# LAN7800-Board.net
KiCad netlist of a schematic drawn in Altium Designer
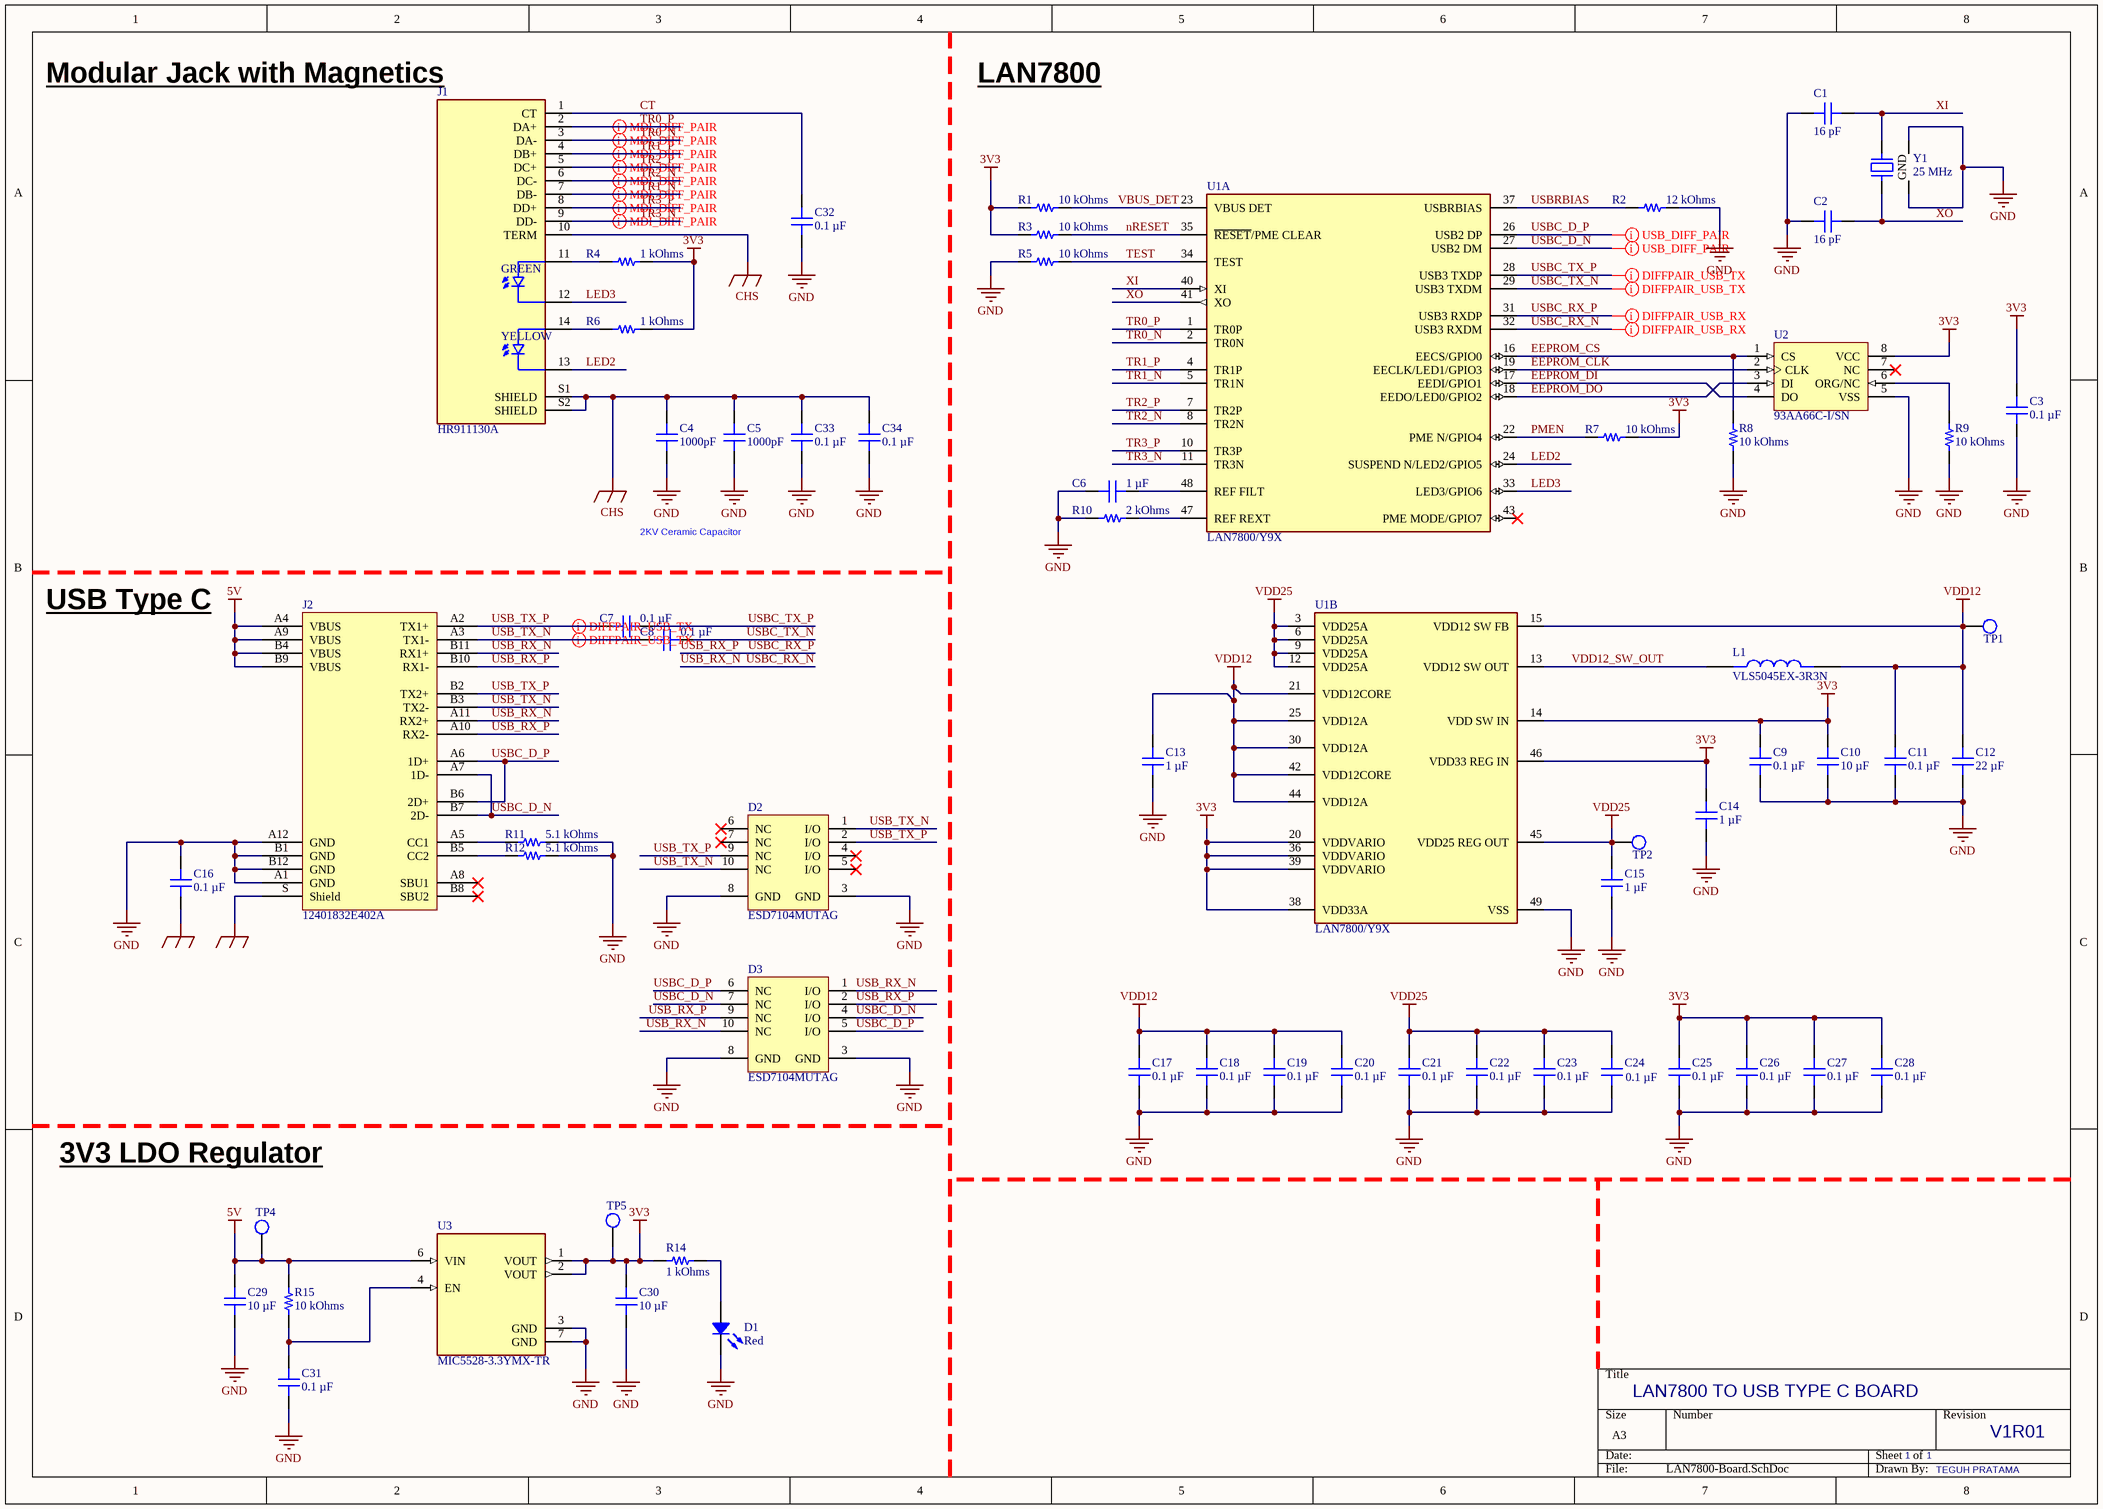
[diagram p0: LAN7800-Board.SchDoc]

(export (version "E")
  (design (tool "Eeschema 10.0.6"))
  (components
    (comp (ref "C1")
      (value "16 pF")
      (footprint "CAP 0402_1005")
      (description "CAP CER 16PF 50V C0G/NP0 0402")
      (fields (field (name "PART NUMBER") "CBR04C160F5GAC") (field (name "MANUFACTURER") "KEMET"))
      (libsource (lib "Celestial Altium Library - altium_library") (part "Capacitor"))
    )
    (comp (ref "C2")
      (value "16 pF")
      (footprint "CAP 0402_1005")
      (description "CAP CER 16PF 50V C0G/NP0 0402")
      (fields (field (name "PART NUMBER") "CBR04C160F5GAC") (field (name "MANUFACTURER") "KEMET"))
      (libsource (lib "Celestial Altium Library - altium_library") (part "Capacitor"))
    )
    (comp (ref "C3")
      (value "0.1 µF")
      (footprint "CAP 0402_1005")
      (description "CAP CER 0402 0.1UF 16V X7R 10%")
      (fields (field (name "PART NUMBER") "C0402C104K4RECAUTO") (field (name "MANUFACTURER") "KEMET"))
      (libsource (lib "Celestial Altium Library - altium_library") (part "Capacitor"))
    )
    (comp (ref "C4")
      (value "1000pF")
      (footprint "CAP 1812_4532 2.8MM")
      (description "CAP CER 1000PF 2.5KV X7R 1812")
      (fields (field (name "PART NUMBER") "1812WC102KAT1A") (field (name "MANUFACTURER") "AVX Corporation"))
      (libsource (lib "Celestial Altium Library - altium_library") (part "Capacitor"))
    )
    (comp (ref "C5")
      (value "1000pF")
      (footprint "CAP 1812_4532 2.8MM")
      (description "CAP CER 1000PF 2.5KV X7R 1812")
      (fields (field (name "PART NUMBER") "1812WC102KAT1A") (field (name "MANUFACTURER") "AVX Corporation"))
      (libsource (lib "Celestial Altium Library - altium_library") (part "Capacitor"))
    )
    (comp (ref "C6")
      (value "1 µF")
      (footprint "CAP 0402_1005")
      (description "CAP CER 1UF 10V X7S 0402")
      (fields
        (field (name "PART NUMBER") "GRM155C71A105KE11D")
        (field (name "MANUFACTURER") "Murata Electronics")
      )
      (libsource (lib "Celestial Altium Library - altium_library") (part "Capacitor"))
    )
    (comp (ref "C7")
      (value "0.1 µF")
      (footprint "CAP 0402_1005")
      (description "CAP CER 0.1UF 50V X5R 0402")
      (fields
        (field (name "PART NUMBER") "CGA2B3X5R1H104M050BB")
        (field (name "MANUFACTURER") "TDK Corporation")
      )
      (libsource (lib "Celestial Altium Library - altium_library") (part "Capacitor"))
    )
    (comp (ref "C8")
      (value "0.1 µF")
      (footprint "CAP 0402_1005")
      (description "CAP CER 0.1UF 50V X5R 0402")
      (fields
        (field (name "PART NUMBER") "CGA2B3X5R1H104M050BB")
        (field (name "MANUFACTURER") "TDK Corporation")
      )
      (libsource (lib "Celestial Altium Library - altium_library") (part "Capacitor"))
    )
    (comp (ref "C9")
      (value "0.1 µF")
      (footprint "CAP 0402_1005")
      (description "CAP CER 0402 0.1UF 16V X7R 10%")
      (fields (field (name "PART NUMBER") "C0402C104K4RECAUTO") (field (name "MANUFACTURER") "KEMET"))
      (libsource (lib "Celestial Altium Library - altium_library") (part "Capacitor"))
    )
    (comp (ref "C10")
      (value "10 µF")
      (footprint "CAP 0603_1608")
      (description "CAP CER 10UF 16V X5R 0603")
      (fields
        (field (name "PART NUMBER") "GRT188R61C106ME13D")
        (field (name "MANUFACTURER") "Murata Electronics")
      )
      (libsource (lib "Celestial Altium Library - altium_library") (part "Capacitor"))
    )
    (comp (ref "C11")
      (value "0.1 µF")
      (footprint "CAP 0402_1005")
      (description "CAP CER 0402 0.1UF 16V X7R 10%")
      (fields (field (name "PART NUMBER") "C0402C104K4RECAUTO") (field (name "MANUFACTURER") "KEMET"))
      (libsource (lib "Celestial Altium Library - altium_library") (part "Capacitor"))
    )
    (comp (ref "C12")
      (value "22 µF")
      (footprint "CAP 0603_1608")
      (description "CAP CER 22UF 10V X5R 0603")
      (fields
        (field (name "PART NUMBER") "C1608X5R1A226M080AC")
        (field (name "MANUFACTURER") "TDK Corporation")
      )
      (libsource (lib "Celestial Altium Library - altium_library") (part "Capacitor"))
    )
    (comp (ref "C13")
      (value "1 µF")
      (footprint "CAP 0402_1005")
      (description "CAP CER 1UF 10V X7S 0402")
      (fields
        (field (name "PART NUMBER") "GRM155C71A105KE11D")
        (field (name "MANUFACTURER") "Murata Electronics")
      )
      (libsource (lib "Celestial Altium Library - altium_library") (part "Capacitor"))
    )
    (comp (ref "C14")
      (value "1 µF")
      (footprint "CAP 0402_1005")
      (description "CAP CER 1UF 10V X7S 0402")
      (fields
        (field (name "PART NUMBER") "GRM155C71A105KE11D")
        (field (name "MANUFACTURER") "Murata Electronics")
      )
      (libsource (lib "Celestial Altium Library - altium_library") (part "Capacitor"))
    )
    (comp (ref "C15")
      (value "1 µF")
      (footprint "CAP 0402_1005")
      (description "CAP CER 1UF 10V X7S 0402")
      (fields
        (field (name "PART NUMBER") "GRM155C71A105KE11D")
        (field (name "MANUFACTURER") "Murata Electronics")
      )
      (libsource (lib "Celestial Altium Library - altium_library") (part "Capacitor"))
    )
    (comp (ref "C16")
      (value "0.1 µF")
      (footprint "CAP 0402_1005")
      (description "CAP CER 0.1UF 50V X5R 0402")
      (fields
        (field (name "PART NUMBER") "CGA2B3X5R1H104M050BB")
        (field (name "MANUFACTURER") "TDK Corporation")
      )
      (libsource (lib "Celestial Altium Library - altium_library") (part "Capacitor"))
    )
    (comp (ref "C17")
      (value "0.1 µF")
      (footprint "CAP 0402_1005")
      (description "CAP CER 0402 0.1UF 16V X7R 10%")
      (fields (field (name "PART NUMBER") "C0402C104K4RECAUTO") (field (name "MANUFACTURER") "KEMET"))
      (libsource (lib "Celestial Altium Library - altium_library") (part "Capacitor"))
    )
    (comp (ref "C18")
      (value "0.1 µF")
      (footprint "CAP 0402_1005")
      (description "CAP CER 0402 0.1UF 16V X7R 10%")
      (fields (field (name "PART NUMBER") "C0402C104K4RECAUTO") (field (name "MANUFACTURER") "KEMET"))
      (libsource (lib "Celestial Altium Library - altium_library") (part "Capacitor"))
    )
    (comp (ref "C19")
      (value "0.1 µF")
      (footprint "CAP 0402_1005")
      (description "CAP CER 0402 0.1UF 16V X7R 10%")
      (fields (field (name "PART NUMBER") "C0402C104K4RECAUTO") (field (name "MANUFACTURER") "KEMET"))
      (libsource (lib "Celestial Altium Library - altium_library") (part "Capacitor"))
    )
    (comp (ref "C20")
      (value "0.1 µF")
      (footprint "CAP 0402_1005")
      (description "CAP CER 0402 0.1UF 16V X7R 10%")
      (fields (field (name "PART NUMBER") "C0402C104K4RECAUTO") (field (name "MANUFACTURER") "KEMET"))
      (libsource (lib "Celestial Altium Library - altium_library") (part "Capacitor"))
    )
    (comp (ref "C21")
      (value "0.1 µF")
      (footprint "CAP 0402_1005")
      (description "CAP CER 0402 0.1UF 16V X7R 10%")
      (fields (field (name "PART NUMBER") "C0402C104K4RECAUTO") (field (name "MANUFACTURER") "KEMET"))
      (libsource (lib "Celestial Altium Library - altium_library") (part "Capacitor"))
    )
    (comp (ref "C22")
      (value "0.1 µF")
      (footprint "CAP 0402_1005")
      (description "CAP CER 0402 0.1UF 16V X7R 10%")
      (fields (field (name "PART NUMBER") "C0402C104K4RECAUTO") (field (name "MANUFACTURER") "KEMET"))
      (libsource (lib "Celestial Altium Library - altium_library") (part "Capacitor"))
    )
    (comp (ref "C23")
      (value "0.1 µF")
      (footprint "CAP 0402_1005")
      (description "CAP CER 0402 0.1UF 16V X7R 10%")
      (fields (field (name "PART NUMBER") "C0402C104K4RECAUTO") (field (name "MANUFACTURER") "KEMET"))
      (libsource (lib "Celestial Altium Library - altium_library") (part "Capacitor"))
    )
    (comp (ref "C24")
      (value "0.1 µF")
      (footprint "CAP 0402_1005")
      (description "CAP CER 0402 0.1UF 16V X7R 10%")
      (fields (field (name "PART NUMBER") "C0402C104K4RECAUTO") (field (name "MANUFACTURER") "KEMET"))
      (libsource (lib "Celestial Altium Library - altium_library") (part "Capacitor"))
    )
    (comp (ref "C25")
      (value "0.1 µF")
      (footprint "CAP 0402_1005")
      (description "CAP CER 0402 0.1UF 16V X7R 10%")
      (fields (field (name "PART NUMBER") "C0402C104K4RECAUTO") (field (name "MANUFACTURER") "KEMET"))
      (libsource (lib "Celestial Altium Library - altium_library") (part "Capacitor"))
    )
    (comp (ref "C26")
      (value "0.1 µF")
      (footprint "CAP 0402_1005")
      (description "CAP CER 0402 0.1UF 16V X7R 10%")
      (fields (field (name "PART NUMBER") "C0402C104K4RECAUTO") (field (name "MANUFACTURER") "KEMET"))
      (libsource (lib "Celestial Altium Library - altium_library") (part "Capacitor"))
    )
    (comp (ref "C27")
      (value "0.1 µF")
      (footprint "CAP 0402_1005")
      (description "CAP CER 0402 0.1UF 16V X7R 10%")
      (fields (field (name "PART NUMBER") "C0402C104K4RECAUTO") (field (name "MANUFACTURER") "KEMET"))
      (libsource (lib "Celestial Altium Library - altium_library") (part "Capacitor"))
    )
    (comp (ref "C28")
      (value "0.1 µF")
      (footprint "CAP 0402_1005")
      (description "CAP CER 0402 0.1UF 16V X7R 10%")
      (fields (field (name "PART NUMBER") "C0402C104K4RECAUTO") (field (name "MANUFACTURER") "KEMET"))
      (libsource (lib "Celestial Altium Library - altium_library") (part "Capacitor"))
    )
    (comp (ref "C29")
      (value "10 µF")
      (footprint "CAP 0603_1608")
      (description "CAP CER 10UF 16V X5R 0603")
      (fields
        (field (name "PART NUMBER") "GRT188R61C106ME13D")
        (field (name "MANUFACTURER") "Murata Electronics")
      )
      (libsource (lib "Celestial Altium Library - altium_library") (part "Capacitor"))
    )
    (comp (ref "C30")
      (value "10 µF")
      (footprint "CAP 0603_1608")
      (description "CAP CER 10UF 16V X5R 0603")
      (fields
        (field (name "PART NUMBER") "GRT188R61C106ME13D")
        (field (name "MANUFACTURER") "Murata Electronics")
      )
      (libsource (lib "Celestial Altium Library - altium_library") (part "Capacitor"))
    )
    (comp (ref "C31")
      (value "0.1 µF")
      (footprint "CAP 0402_1005")
      (description "CAP CER 0402 0.1UF 16V X7R 10%")
      (fields (field (name "PART NUMBER") "C0402C104K4RECAUTO") (field (name "MANUFACTURER") "KEMET"))
      (libsource (lib "Celestial Altium Library - altium_library") (part "Capacitor"))
    )
    (comp (ref "C32")
      (value "0.1 µF")
      (footprint "CAP 0402_1005")
      (description "CAP CER 0402 0.1UF 16V X7R 10%")
      (fields (field (name "PART NUMBER") "C0402C104K4RECAUTO") (field (name "MANUFACTURER") "KEMET"))
      (libsource (lib "Celestial Altium Library - altium_library") (part "Capacitor"))
    )
    (comp (ref "C33")
      (value "0.1 µF")
      (footprint "CAP 0402_1005")
      (description "CAP CER 0402 0.1UF 16V X7R 10%")
      (fields (field (name "PART NUMBER") "C0402C104K4RECAUTO") (field (name "MANUFACTURER") "KEMET"))
      (libsource (lib "Celestial Altium Library - altium_library") (part "Capacitor"))
    )
    (comp (ref "C34")
      (value "0.1 µF")
      (footprint "CAP 0402_1005")
      (description "CAP CER 0402 0.1UF 16V X7R 10%")
      (fields (field (name "PART NUMBER") "C0402C104K4RECAUTO") (field (name "MANUFACTURER") "KEMET"))
      (libsource (lib "Celestial Altium Library - altium_library") (part "Capacitor"))
    )
    (comp (ref "D1")
      (value "Red")
      (footprint "LED 0603_1608 RED")
      (description "HIGH BRIGHTNESS LENS TYPE, RED C")
      (fields (field (name "PART NUMBER") "CSL0902VT1C") (field (name "MANUFACTURER") "Rohm Semiconductor"))
      (libsource (lib "Celestial Altium Library - altium_library") (part "LED"))
    )
    (comp (ref "D2")
      (value "ESD7104MUTAG")
      (footprint "ONSC-UDFN-10-517BB-01_V")
      (fields (field (name "MANUFACTURER") "On Semiconductor"))
      (libsource (lib "Diodes - Transient Voltage Supressor") (part "ESD7104MUTAG"))
    )
    (comp (ref "D3")
      (value "ESD7104MUTAG")
      (footprint "ONSC-UDFN-10-517BB-01_V")
      (fields (field (name "MANUFACTURER") "On Semiconductor"))
      (libsource (lib "Diodes - Transient Voltage Supressor") (part "ESD7104MUTAG"))
    )
    (comp (ref "J1")
      (value "HR911130A")
      (footprint "HANRUN_HR911130A")
      (description "Gigabit Ethernet with Magnetics")
      (fields (field (name "MF") "hanrun"))
      (libsource (lib "Connector - Modular Jack with Magnetics") (part "HR911130A"))
    )
    (comp (ref "J2")
      (value "12401832E402A")
      (footprint "GCT_USB4056-03-A_REVA2")
      (description "24 Position Hybrid Top Mount USB Type C 3.2 Gen Receptacle")
      (fields
        (field (name "MANUFACTURER") "Global Connector Technology")
        (field (name "MANUFACTURER PART NUMBER") "USB4056-03-A")
      )
      (libsource (lib "Connector - USB") (part "USB4056-03-A"))
    )
    (comp (ref "L1")
      (value "VLS5045EX-3R3N")
      (footprint "IND_VLS5045EX-3R3N")
      (description "General Purpose Inductor, 3.3uH, 30%, 1 Element, Ferrite-Core, SMD, 2020")
      (fields (field (name "MF") "TDK"))
      (libsource (lib "Inductor") (part "VLS5045EX-3R3N"))
    )
    (comp (ref "R1")
      (value "10 kOhms")
      (footprint "RES 0402_1005")
      (description "RES 10K OHM 0.1% 1/10W 0402")
      (fields
        (field (name "PART NUMBER") "RP73PF1E10KBTD")
        (field (name "MANUFACTURER") "TE Connectivity Passive Product")
      )
      (libsource (lib "Celestial Altium Library - altium_library") (part "Resistor"))
    )
    (comp (ref "R2")
      (value "12 kOhms")
      (footprint "RES 0402_1005")
      (description "RES SMD 12K OHM 0.1% 1/16W 0402")
      (fields
        (field (name "PART NUMBER") "CPF0402B12KE1")
        (field (name "MANUFACTURER") "TE Connectivity Passive Product")
      )
      (libsource (lib "Celestial Altium Library - altium_library") (part "Resistor"))
    )
    (comp (ref "R3")
      (value "10 kOhms")
      (footprint "RES 0402_1005")
      (description "RES 10K OHM 0.1% 1/10W 0402")
      (fields
        (field (name "PART NUMBER") "RP73PF1E10KBTD")
        (field (name "MANUFACTURER") "TE Connectivity Passive Product")
      )
      (libsource (lib "Celestial Altium Library - altium_library") (part "Resistor"))
    )
    (comp (ref "R4")
      (value "1 kOhms")
      (footprint "RES 0402_1005")
      (description "RES SMD 1K OHM 0.1% 1/16W 0402")
      (fields (field (name "PART NUMBER") "AT0402BRD071KL") (field (name "MANUFACTURER") "Yageo"))
      (libsource (lib "Celestial Altium Library - altium_library") (part "Resistor"))
    )
    (comp (ref "R5")
      (value "10 kOhms")
      (footprint "RES 0402_1005")
      (description "RES 10K OHM 0.1% 1/10W 0402")
      (fields
        (field (name "PART NUMBER") "RP73PF1E10KBTD")
        (field (name "MANUFACTURER") "TE Connectivity Passive Product")
      )
      (libsource (lib "Celestial Altium Library - altium_library") (part "Resistor"))
    )
    (comp (ref "R6")
      (value "1 kOhms")
      (footprint "RES 0402_1005")
      (description "RES SMD 1K OHM 0.1% 1/16W 0402")
      (fields (field (name "PART NUMBER") "AT0402BRD071KL") (field (name "MANUFACTURER") "Yageo"))
      (libsource (lib "Celestial Altium Library - altium_library") (part "Resistor"))
    )
    (comp (ref "R7")
      (value "10 kOhms")
      (footprint "RES 0402_1005")
      (description "RES 10K OHM 0.1% 1/10W 0402")
      (fields
        (field (name "PART NUMBER") "RP73PF1E10KBTD")
        (field (name "MANUFACTURER") "TE Connectivity Passive Product")
      )
      (libsource (lib "Celestial Altium Library - altium_library") (part "Resistor"))
    )
    (comp (ref "R8")
      (value "10 kOhms")
      (footprint "RES 0402_1005")
      (description "RES 10K OHM 0.1% 1/10W 0402")
      (fields
        (field (name "PART NUMBER") "RP73PF1E10KBTD")
        (field (name "MANUFACTURER") "TE Connectivity Passive Product")
      )
      (libsource (lib "Celestial Altium Library - altium_library") (part "Resistor"))
    )
    (comp (ref "R9")
      (value "10 kOhms")
      (footprint "RES 0402_1005")
      (description "RES 10K OHM 0.1% 1/10W 0402")
      (fields
        (field (name "PART NUMBER") "RP73PF1E10KBTD")
        (field (name "MANUFACTURER") "TE Connectivity Passive Product")
      )
      (libsource (lib "Celestial Altium Library - altium_library") (part "Resistor"))
    )
    (comp (ref "R10")
      (value "2 kOhms")
      (footprint "RES 0402_1005")
      (description "RES SMD 2K OHM 0.1% 1/16W 0402")
      (fields
        (field (name "PART NUMBER") "CPF0402B2K0E1")
        (field (name "MANUFACTURER") "TE Connectivity Passive Product")
      )
      (libsource (lib "Celestial Altium Library - altium_library") (part "Resistor"))
    )
    (comp (ref "R11")
      (value "5.1 kOhms")
      (footprint "RES 0402_1005")
      (description "RES 5.1K OHM 5% 1/16W 0402")
      (fields (field (name "PART NUMBER") "RC0402JR-075K1L") (field (name "MANUFACTURER") "Yageo"))
      (libsource (lib "Celestial Altium Library - altium_library") (part "Resistor"))
    )
    (comp (ref "R12")
      (value "5.1 kOhms")
      (footprint "RES 0402_1005")
      (description "RES 5.1K OHM 5% 1/16W 0402")
      (fields (field (name "PART NUMBER") "RC0402JR-075K1L") (field (name "MANUFACTURER") "Yageo"))
      (libsource (lib "Celestial Altium Library - altium_library") (part "Resistor"))
    )
    (comp (ref "R14")
      (value "1 kOhms")
      (footprint "RES 0402_1005")
      (description "RES SMD 1K OHM 0.1% 1/16W 0402")
      (fields (field (name "PART NUMBER") "AT0402BRD071KL") (field (name "MANUFACTURER") "Yageo"))
      (libsource (lib "Celestial Altium Library - altium_library") (part "Resistor"))
    )
    (comp (ref "R15")
      (value "10 kOhms")
      (footprint "RES 0402_1005")
      (description "RES 10K OHM 0.1% 1/10W 0402")
      (fields
        (field (name "PART NUMBER") "RP73PF1E10KBTD")
        (field (name "MANUFACTURER") "TE Connectivity Passive Product")
      )
      (libsource (lib "Celestial Altium Library - altium_library") (part "Resistor"))
    )
    (comp (ref "TP1")
      (value "TestPoint")
      (footprint "Rounded 1.7mm X 1.7mm")
      (libsource (lib "TestPoint") (part "TestPoint"))
    )
    (comp (ref "TP2")
      (value "TestPoint")
      (footprint "Rounded 1.7mm X 1.7mm")
      (libsource (lib "TestPoint") (part "TestPoint"))
    )
    (comp (ref "TP4")
      (value "TestPoint")
      (footprint "Rounded 1.7mm X 1.7mm")
      (libsource (lib "TestPoint") (part "TestPoint"))
    )
    (comp (ref "TP5")
      (value "TestPoint")
      (footprint "Rounded 1.7mm X 1.7mm")
      (libsource (lib "TestPoint") (part "TestPoint"))
    )
    (comp (ref "U1")
      (value "LAN7800/Y9X")
      (footprint "FP-48SQFN-5304-7x7B-IPC_B")
      (description "USB Bus Controller, CMOS")
      (fields (field (name "MANUFACTURER") "Microchip"))
      (libsource (lib "Integrated Circuit - Ethernet Controller") (part "LAN7800/Y9X"))
    )
    (comp (ref "U2")
      (value "93AA66C-I/SN")
      (footprint "SOIC-SN8_N")
      (description "Microwire Serial EEPROM Family, 1.8 to 5.5V, 3 MHz, -40°Cto 125°C, SOIC-8, RoHS")
      (fields (field (name "MANUFACTURER") "Microchip"))
      (libsource (lib "Memory") (part "93AA66C-I/SN"))
    )
    (comp (ref "U3")
      (value "MIC5528-3.3YMX-TR")
      (footprint "SON40P120X120X60-7N")
      (description "Single 500mA LDO w/ Auto Discharge & Internal Enable Pulldown")
      (fields (field (name "MANUFACTURER") "Microchip"))
      (libsource (lib "Voltage Regulator - Linear") (part "MIC5528-3.3YMX-TR"))
    )
    (comp (ref "Y1")
      (value "25 MHz")
      (footprint "EPSON TSX-3225")
      (description "CRYSTAL 25.0000MHZ 8PF SMD")
      (fields (field (name "PART NUMBER") "TSX-3225 25.0000MF20X-AJ3") (field (name "MANUFACTURER") "EPSON"))
      (libsource (lib "Celestial Altium Library - altium_library") (part "Epson Crystal TSX-3225"))
    )
  )
  (nets
    (net (code "1") (name "/CT") (class "Default")
      (node (ref "C32") (pin "2") (pinfunction "2_2") (pintype "passive"))
      (node (ref "J1") (pin "1") (pinfunction "CT_1") (pintype "passive"))
    )
    (net (code "2") (name "/EEPROM_CLK") (class "Default")
      (node (ref "U1") (pin "19") (pinfunction "EECLK/LED1/GPIO3_19") (pintype "bidirectional"))
      (node (ref "U2") (pin "2") (pinfunction "CLK_2") (pintype "input"))
    )
    (net (code "3") (name "/EEPROM_CS") (class "Default")
      (node (ref "R8") (pin "2") (pinfunction "2_2") (pintype "passive"))
      (node (ref "U1") (pin "16") (pinfunction "EECS/GPIO0_16") (pintype "bidirectional"))
      (node (ref "U2") (pin "1") (pinfunction "CS_1") (pintype "input"))
    )
    (net (code "4") (name "/EEPROM_DI") (class "Default")
      (node (ref "U1") (pin "17") (pinfunction "EEDI/GPIO1_17") (pintype "bidirectional"))
      (node (ref "U2") (pin "4") (pinfunction "DO_4") (pintype "tri_state"))
    )
    (net (code "5") (name "/EEPROM_DO") (class "Default")
      (node (ref "U1") (pin "18") (pinfunction "EEDO/LED0/GPIO2_18") (pintype "bidirectional"))
      (node (ref "U2") (pin "3") (pinfunction "DI_3") (pintype "input"))
    )
    (net (code "6") (name "/LED2") (class "Default")
      (node (ref "J1") (pin "13") (pinfunction "13_13") (pintype "passive"))
      (node (ref "U1") (pin "24") (pinfunction "SUSPEND_N/LED2/GPIO5_24") (pintype "bidirectional"))
    )
    (net (code "7") (name "/LED3") (class "Default")
      (node (ref "J1") (pin "12") (pinfunction "12_12") (pintype "passive"))
      (node (ref "U1") (pin "33") (pinfunction "LED3/GPIO6_33") (pintype "bidirectional"))
    )
    (net (code "8") (name "/PMEN") (class "Default")
      (node (ref "R7") (pin "2") (pinfunction "2_2") (pintype "passive"))
      (node (ref "U1") (pin "22") (pinfunction "PME_N/GPIO4_22") (pintype "bidirectional"))
    )
    (net (code "9") (name "/TEST") (class "Default")
      (node (ref "R5") (pin "1") (pinfunction "1_1") (pintype "passive"))
      (node (ref "U1") (pin "34") (pinfunction "TEST_34") (pintype "passive"))
    )
    (net (code "10") (name "/TR0_N") (class "Default")
      (node (ref "J1") (pin "3") (pinfunction "DA-_3") (pintype "passive"))
      (node (ref "U1") (pin "2") (pinfunction "TR0N_2") (pintype "passive"))
    )
    (net (code "11") (name "/TR0_P") (class "Default")
      (node (ref "J1") (pin "2") (pinfunction "DA+_2") (pintype "passive"))
      (node (ref "U1") (pin "1") (pinfunction "TR0P_1") (pintype "passive"))
    )
    (net (code "12") (name "/TR1_N") (class "Default")
      (node (ref "J1") (pin "7") (pinfunction "DB-_7") (pintype "passive"))
      (node (ref "U1") (pin "5") (pinfunction "TR1N_5") (pintype "passive"))
    )
    (net (code "13") (name "/TR1_P") (class "Default")
      (node (ref "J1") (pin "4") (pinfunction "DB+_4") (pintype "passive"))
      (node (ref "U1") (pin "4") (pinfunction "TR1P_4") (pintype "passive"))
    )
    (net (code "14") (name "/TR2_N") (class "Default")
      (node (ref "J1") (pin "6") (pinfunction "DC-_6") (pintype "passive"))
      (node (ref "U1") (pin "8") (pinfunction "TR2N_8") (pintype "passive"))
    )
    (net (code "15") (name "/TR2_P") (class "Default")
      (node (ref "J1") (pin "5") (pinfunction "DC+_5") (pintype "passive"))
      (node (ref "U1") (pin "7") (pinfunction "TR2P_7") (pintype "passive"))
    )
    (net (code "16") (name "/TR3_N") (class "Default")
      (node (ref "J1") (pin "9") (pinfunction "DD-_9") (pintype "passive"))
      (node (ref "U1") (pin "11") (pinfunction "TR3N_11") (pintype "passive"))
    )
    (net (code "17") (name "/TR3_P") (class "Default")
      (node (ref "J1") (pin "8") (pinfunction "DD+_8") (pintype "passive"))
      (node (ref "U1") (pin "10") (pinfunction "TR3P_10") (pintype "passive"))
    )
    (net (code "18") (name "/USBC_D_N") (class "Default")
      (node (ref "D3") (pin "4") (pinfunction "I/O_4") (pintype "passive"))
      (node (ref "D3") (pin "7") (pinfunction "NC_7") (pintype "passive"))
      (node (ref "J2") (pin "A7") (pinfunction "1D-_A7") (pintype "passive"))
      (node (ref "J2") (pin "B7") (pinfunction "2D-_B7") (pintype "passive"))
      (node (ref "U1") (pin "27") (pinfunction "USB2_DM_27") (pintype "passive"))
    )
    (net (code "19") (name "/USBC_D_P") (class "Default")
      (node (ref "D3") (pin "5") (pinfunction "I/O_5") (pintype "passive"))
      (node (ref "D3") (pin "6") (pinfunction "NC_6") (pintype "passive"))
      (node (ref "J2") (pin "A6") (pinfunction "1D+_A6") (pintype "passive"))
      (node (ref "J2") (pin "B6") (pinfunction "2D+_B6") (pintype "passive"))
      (node (ref "U1") (pin "26") (pinfunction "USB2_DP_26") (pintype "passive"))
    )
    (net (code "20") (name "/USBC_RX_N") (class "Default")
      (node (ref "D3") (pin "1") (pinfunction "I/O_1") (pintype "passive"))
      (node (ref "D3") (pin "10") (pinfunction "NC_10") (pintype "passive"))
      (node (ref "J2") (pin "A11") (pinfunction "RX2+_A11") (pintype "passive"))
      (node (ref "J2") (pin "B11") (pinfunction "RX1+_B11") (pintype "power_in"))
      (node (ref "U1") (pin "32") (pinfunction "USB3_RXDM_32") (pintype "passive"))
    )
    (net (code "21") (name "/USBC_RX_P") (class "Default")
      (node (ref "D3") (pin "2") (pinfunction "I/O_2") (pintype "passive"))
      (node (ref "D3") (pin "9") (pinfunction "NC_9") (pintype "passive"))
      (node (ref "J2") (pin "A10") (pinfunction "RX2-_A10") (pintype "passive"))
      (node (ref "J2") (pin "B10") (pinfunction "RX1-_B10") (pintype "power_in"))
      (node (ref "U1") (pin "31") (pinfunction "USB3_RXDP_31") (pintype "passive"))
    )
    (net (code "22") (name "/USBC_TX_N") (class "Default")
      (node (ref "C8") (pin "1") (pinfunction "1_1") (pintype "passive"))
      (node (ref "U1") (pin "29") (pinfunction "USB3_TXDM_29") (pintype "passive"))
    )
    (net (code "23") (name "/USBC_TX_P") (class "Default")
      (node (ref "C7") (pin "1") (pinfunction "1_1") (pintype "passive"))
      (node (ref "U1") (pin "28") (pinfunction "USB3_TXDP_28") (pintype "passive"))
    )
    (net (code "24") (name "/USBRBIAS") (class "Default")
      (node (ref "R2") (pin "1") (pinfunction "1_1") (pintype "passive"))
      (node (ref "U1") (pin "37") (pinfunction "USBRBIAS_37") (pintype "passive"))
    )
    (net (code "25") (name "/USB_TX_N") (class "Default")
      (node (ref "C8") (pin "2") (pinfunction "2_2") (pintype "passive"))
      (node (ref "D2") (pin "1") (pinfunction "I/O_1") (pintype "passive"))
      (node (ref "D2") (pin "10") (pinfunction "NC_10") (pintype "passive"))
      (node (ref "J2") (pin "A3") (pinfunction "TX1-_A3") (pintype "passive"))
      (node (ref "J2") (pin "B3") (pinfunction "TX2-_B3") (pintype "passive"))
    )
    (net (code "26") (name "/USB_TX_P") (class "Default")
      (node (ref "C7") (pin "2") (pinfunction "2_2") (pintype "passive"))
      (node (ref "D2") (pin "2") (pinfunction "I/O_2") (pintype "passive"))
      (node (ref "D2") (pin "9") (pinfunction "NC_9") (pintype "passive"))
      (node (ref "J2") (pin "A2") (pinfunction "TX1+_A2") (pintype "passive"))
      (node (ref "J2") (pin "B2") (pinfunction "TX2+_B2") (pintype "passive"))
    )
    (net (code "27") (name "/VBUS_DET") (class "Default")
      (node (ref "R1") (pin "1") (pinfunction "1_1") (pintype "passive"))
      (node (ref "U1") (pin "23") (pinfunction "VBUS_DET_23") (pintype "power_in"))
    )
    (net (code "28") (name "/VDD12_SW_OUT") (class "Default")
      (node (ref "L1") (pin "1") (pinfunction "1_1") (pintype "passive"))
      (node (ref "U1") (pin "13") (pinfunction "VDD12_SW_OUT_13") (pintype "power_in"))
    )
    (net (code "29") (name "/XI") (class "Default")
      (node (ref "C1") (pin "2") (pinfunction "2_2") (pintype "passive"))
      (node (ref "U1") (pin "40") (pinfunction "XI_40") (pintype "input"))
      (node (ref "Y1") (pin "3") (pinfunction "3_3") (pintype "passive"))
    )
    (net (code "30") (name "/XO") (class "Default")
      (node (ref "C2") (pin "2") (pinfunction "2_2") (pintype "passive"))
      (node (ref "U1") (pin "41") (pinfunction "XO_41") (pintype "output"))
      (node (ref "Y1") (pin "1") (pinfunction "1_1") (pintype "passive"))
    )
    (net (code "31") (name "/nRESET") (class "Default")
      (node (ref "R3") (pin "1") (pinfunction "1_1") (pintype "passive"))
      (node (ref "U1") (pin "35") (pinfunction "~{RESET}/PME_CLEAR_35") (pintype "passive"))
    )
    (net (code "32") (name "3V3") (class "Default")
      (node (ref "C10") (pin "2") (pinfunction "2_2") (pintype "passive"))
      (node (ref "C14") (pin "2") (pinfunction "2_2") (pintype "passive"))
      (node (ref "C25") (pin "2") (pinfunction "2_2") (pintype "passive"))
      (node (ref "C26") (pin "2") (pinfunction "2_2") (pintype "passive"))
      (node (ref "C27") (pin "2") (pinfunction "2_2") (pintype "passive"))
      (node (ref "C28") (pin "2") (pinfunction "2_2") (pintype "passive"))
      (node (ref "C3") (pin "2") (pinfunction "2_2") (pintype "passive"))
      (node (ref "C30") (pin "2") (pinfunction "2_2") (pintype "passive"))
      (node (ref "C9") (pin "2") (pinfunction "2_2") (pintype "passive"))
      (node (ref "R1") (pin "2") (pinfunction "2_2") (pintype "passive"))
      (node (ref "R14") (pin "2") (pinfunction "2_2") (pintype "passive"))
      (node (ref "R3") (pin "2") (pinfunction "2_2") (pintype "passive"))
      (node (ref "R4") (pin "2") (pinfunction "2_2") (pintype "passive"))
      (node (ref "R6") (pin "2") (pinfunction "2_2") (pintype "passive"))
      (node (ref "R7") (pin "1") (pinfunction "1_1") (pintype "passive"))
      (node (ref "TP5") (pin "1") (pinfunction "1_1") (pintype "passive"))
      (node (ref "U1") (pin "14") (pinfunction "VDD_SW_IN_14") (pintype "power_in"))
      (node (ref "U1") (pin "20") (pinfunction "VDDVARIO_20") (pintype "power_in"))
      (node (ref "U1") (pin "36") (pinfunction "VDDVARIO_36") (pintype "power_in"))
      (node (ref "U1") (pin "38") (pinfunction "VDD33A_38") (pintype "power_in"))
      (node (ref "U1") (pin "39") (pinfunction "VDDVARIO_39") (pintype "power_in"))
      (node (ref "U1") (pin "46") (pinfunction "VDD33_REG_IN_46") (pintype "power_in"))
      (node (ref "U2") (pin "8") (pinfunction "VCC_8") (pintype "power_in"))
      (node (ref "U3") (pin "1") (pinfunction "VOUT_1") (pintype "output"))
      (node (ref "U3") (pin "2") (pinfunction "VOUT_2") (pintype "output"))
    )
    (net (code "33") (name "5V") (class "Default")
      (node (ref "C29") (pin "2") (pinfunction "2_2") (pintype "passive"))
      (node (ref "J2") (pin "A4") (pinfunction "VBUS_A4") (pintype "passive"))
      (node (ref "J2") (pin "A9") (pinfunction "VBUS_A9") (pintype "power_in"))
      (node (ref "J2") (pin "B4") (pinfunction "VBUS_B4") (pintype "passive"))
      (node (ref "J2") (pin "B9") (pinfunction "VBUS_B9") (pintype "power_in"))
      (node (ref "R15") (pin "2") (pinfunction "2_2") (pintype "passive"))
      (node (ref "TP4") (pin "1") (pinfunction "1_1") (pintype "passive"))
      (node (ref "U3") (pin "6") (pinfunction "VIN_6") (pintype "input"))
    )
    (net (code "34") (name "CHS") (class "Default")
      (node (ref "C33") (pin "2") (pinfunction "2_2") (pintype "passive"))
      (node (ref "C34") (pin "2") (pinfunction "2_2") (pintype "passive"))
      (node (ref "C4") (pin "2") (pinfunction "2_2") (pintype "passive"))
      (node (ref "C5") (pin "2") (pinfunction "2_2") (pintype "passive"))
      (node (ref "J1") (pin "10") (pinfunction "TERM_10") (pintype "passive"))
      (node (ref "J1") (pin "S1") (pinfunction "SHIELD_S1") (pintype "passive"))
      (node (ref "J1") (pin "S2") (pinfunction "SHIELD_S2") (pintype "passive"))
    )
    (net (code "35") (name "EARTH") (class "Default")
      (node (ref "C16") (pin "1") (pinfunction "1_1") (pintype "passive"))
      (node (ref "J2") (pin "S") (pinfunction "Shield_S") (pintype "power_in"))
    )
    (net (code "36") (name "GND") (class "Default")
      (node (ref "C1") (pin "1") (pinfunction "1_1") (pintype "passive"))
      (node (ref "C10") (pin "1") (pinfunction "1_1") (pintype "passive"))
      (node (ref "C11") (pin "1") (pinfunction "1_1") (pintype "passive"))
      (node (ref "C12") (pin "1") (pinfunction "1_1") (pintype "passive"))
      (node (ref "C13") (pin "1") (pinfunction "1_1") (pintype "passive"))
      (node (ref "C14") (pin "1") (pinfunction "1_1") (pintype "passive"))
      (node (ref "C15") (pin "1") (pinfunction "1_1") (pintype "passive"))
      (node (ref "C16") (pin "2") (pinfunction "2_2") (pintype "passive"))
      (node (ref "C17") (pin "1") (pinfunction "1_1") (pintype "passive"))
      (node (ref "C18") (pin "1") (pinfunction "1_1") (pintype "passive"))
      (node (ref "C19") (pin "1") (pinfunction "1_1") (pintype "passive"))
      (node (ref "C2") (pin "1") (pinfunction "1_1") (pintype "passive"))
      (node (ref "C20") (pin "1") (pinfunction "1_1") (pintype "passive"))
      (node (ref "C21") (pin "1") (pinfunction "1_1") (pintype "passive"))
      (node (ref "C22") (pin "1") (pinfunction "1_1") (pintype "passive"))
      (node (ref "C23") (pin "1") (pinfunction "1_1") (pintype "passive"))
      (node (ref "C24") (pin "1") (pinfunction "1_1") (pintype "passive"))
      (node (ref "C25") (pin "1") (pinfunction "1_1") (pintype "passive"))
      (node (ref "C26") (pin "1") (pinfunction "1_1") (pintype "passive"))
      (node (ref "C27") (pin "1") (pinfunction "1_1") (pintype "passive"))
      (node (ref "C28") (pin "1") (pinfunction "1_1") (pintype "passive"))
      (node (ref "C29") (pin "1") (pinfunction "1_1") (pintype "passive"))
      (node (ref "C3") (pin "1") (pinfunction "1_1") (pintype "passive"))
      (node (ref "C30") (pin "1") (pinfunction "1_1") (pintype "passive"))
      (node (ref "C31") (pin "1") (pinfunction "1_1") (pintype "passive"))
      (node (ref "C32") (pin "1") (pinfunction "1_1") (pintype "passive"))
      (node (ref "C33") (pin "1") (pinfunction "1_1") (pintype "passive"))
      (node (ref "C34") (pin "1") (pinfunction "1_1") (pintype "passive"))
      (node (ref "C4") (pin "1") (pinfunction "1_1") (pintype "passive"))
      (node (ref "C5") (pin "1") (pinfunction "1_1") (pintype "passive"))
      (node (ref "C6") (pin "1") (pinfunction "1_1") (pintype "passive"))
      (node (ref "C9") (pin "1") (pinfunction "1_1") (pintype "passive"))
      (node (ref "D1") (pin "2") (pinfunction "2_2") (pintype "passive"))
      (node (ref "D2") (pin "3") (pinfunction "GND_3") (pintype "power_in"))
      (node (ref "D2") (pin "8") (pinfunction "GND_8") (pintype "power_in"))
      (node (ref "D3") (pin "3") (pinfunction "GND_3") (pintype "power_in"))
      (node (ref "D3") (pin "8") (pinfunction "GND_8") (pintype "power_in"))
      (node (ref "J2") (pin "A1") (pinfunction "GND_A1") (pintype "passive"))
      (node (ref "J2") (pin "A12") (pinfunction "GND_A12") (pintype "power_in"))
      (node (ref "J2") (pin "B1") (pinfunction "GND_B1") (pintype "passive"))
      (node (ref "J2") (pin "B12") (pinfunction "GND_B12") (pintype "power_in"))
      (node (ref "R10") (pin "1") (pinfunction "1_1") (pintype "passive"))
      (node (ref "R11") (pin "2") (pinfunction "2_2") (pintype "passive"))
      (node (ref "R12") (pin "2") (pinfunction "2_2") (pintype "passive"))
      (node (ref "R2") (pin "2") (pinfunction "2_2") (pintype "passive"))
      (node (ref "R5") (pin "2") (pinfunction "2_2") (pintype "passive"))
      (node (ref "R8") (pin "1") (pinfunction "1_1") (pintype "passive"))
      (node (ref "R9") (pin "1") (pinfunction "1_1") (pintype "passive"))
      (node (ref "U1") (pin "49") (pinfunction "VSS_49") (pintype "power_in"))
      (node (ref "U2") (pin "5") (pinfunction "VSS_5") (pintype "power_in"))
      (node (ref "U3") (pin "3") (pinfunction "GND_3") (pintype "power_in"))
      (node (ref "U3") (pin "7") (pinfunction "GND_7") (pintype "power_in"))
      (node (ref "Y1") (pin "2") (pinfunction "GND_2") (pintype "passive"))
      (node (ref "Y1") (pin "4") (pinfunction "GND_4") (pintype "passive"))
    )
    (net (code "37") (name "Net-(D1-Pad1)") (class "Default")
      (node (ref "D1") (pin "1") (pinfunction "1_1") (pintype "passive"))
      (node (ref "R14") (pin "1") (pinfunction "1_1") (pintype "passive"))
    )
    (net (code "38") (name "Net-(J1-Pad11)") (class "Default")
      (node (ref "J1") (pin "11") (pinfunction "11_11") (pintype "passive"))
      (node (ref "R4") (pin "1") (pinfunction "1_1") (pintype "passive"))
    )
    (net (code "39") (name "Net-(J1-Pad14)") (class "Default")
      (node (ref "J1") (pin "14") (pinfunction "14_14") (pintype "passive"))
      (node (ref "R6") (pin "1") (pinfunction "1_1") (pintype "passive"))
    )
    (net (code "40") (name "Net-(J2-CC1)") (class "Default")
      (node (ref "J2") (pin "A5") (pinfunction "CC1_A5") (pintype "power_in"))
      (node (ref "R11") (pin "1") (pinfunction "1_1") (pintype "passive"))
    )
    (net (code "41") (name "Net-(J2-CC2)") (class "Default")
      (node (ref "J2") (pin "B5") (pinfunction "CC2_B5") (pintype "power_in"))
      (node (ref "R12") (pin "1") (pinfunction "1_1") (pintype "passive"))
    )
    (net (code "42") (name "Net-(U1A-REF_FILT)") (class "Default")
      (node (ref "C6") (pin "2") (pinfunction "2_2") (pintype "passive"))
      (node (ref "U1") (pin "48") (pinfunction "REF_FILT_48") (pintype "passive"))
    )
    (net (code "43") (name "Net-(U1A-REF_REXT)") (class "Default")
      (node (ref "R10") (pin "2") (pinfunction "2_2") (pintype "passive"))
      (node (ref "U1") (pin "47") (pinfunction "REF_REXT_47") (pintype "passive"))
    )
    (net (code "44") (name "Net-(U2-ORG{slash}NC)") (class "Default")
      (node (ref "R9") (pin "2") (pinfunction "2_2") (pintype "passive"))
      (node (ref "U2") (pin "6") (pinfunction "ORG/NC_6") (pintype "input"))
    )
    (net (code "45") (name "Net-(U3-EN)") (class "Default")
      (node (ref "C31") (pin "2") (pinfunction "2_2") (pintype "passive"))
      (node (ref "R15") (pin "1") (pinfunction "1_1") (pintype "passive"))
      (node (ref "U3") (pin "4") (pinfunction "EN_4") (pintype "input"))
    )
    (net (code "46") (name "VDD12") (class "Default")
      (node (ref "C11") (pin "2") (pinfunction "2_2") (pintype "passive"))
      (node (ref "C12") (pin "2") (pinfunction "2_2") (pintype "passive"))
      (node (ref "C13") (pin "2") (pinfunction "2_2") (pintype "passive"))
      (node (ref "C17") (pin "2") (pinfunction "2_2") (pintype "passive"))
      (node (ref "C18") (pin "2") (pinfunction "2_2") (pintype "passive"))
      (node (ref "C19") (pin "2") (pinfunction "2_2") (pintype "passive"))
      (node (ref "C20") (pin "2") (pinfunction "2_2") (pintype "passive"))
      (node (ref "L1") (pin "2") (pinfunction "2_2") (pintype "passive"))
      (node (ref "TP1") (pin "1") (pinfunction "1_1") (pintype "passive"))
      (node (ref "U1") (pin "15") (pinfunction "VDD12_SW_FB_15") (pintype "power_in"))
      (node (ref "U1") (pin "21") (pinfunction "VDD12CORE_21") (pintype "power_in"))
      (node (ref "U1") (pin "25") (pinfunction "VDD12A_25") (pintype "power_in"))
      (node (ref "U1") (pin "30") (pinfunction "VDD12A_30") (pintype "power_in"))
      (node (ref "U1") (pin "42") (pinfunction "VDD12CORE_42") (pintype "power_in"))
      (node (ref "U1") (pin "44") (pinfunction "VDD12A_44") (pintype "power_in"))
    )
    (net (code "47") (name "VDD25") (class "Default")
      (node (ref "C15") (pin "2") (pinfunction "2_2") (pintype "passive"))
      (node (ref "C21") (pin "2") (pinfunction "2_2") (pintype "passive"))
      (node (ref "C22") (pin "2") (pinfunction "2_2") (pintype "passive"))
      (node (ref "C23") (pin "2") (pinfunction "2_2") (pintype "passive"))
      (node (ref "C24") (pin "2") (pinfunction "2_2") (pintype "passive"))
      (node (ref "TP2") (pin "1") (pinfunction "1_1") (pintype "passive"))
      (node (ref "U1") (pin "12") (pinfunction "VDD25A_12") (pintype "power_in"))
      (node (ref "U1") (pin "3") (pinfunction "VDD25A_3") (pintype "power_in"))
      (node (ref "U1") (pin "45") (pinfunction "VDD25_REG_OUT_45") (pintype "power_in"))
      (node (ref "U1") (pin "6") (pinfunction "VDD25A_6") (pintype "power_in"))
      (node (ref "U1") (pin "9") (pinfunction "VDD25A_9") (pintype "power_in"))
    )
    (net (code "48") (name "unconnected-(D2-I{slash}O-Pad4)") (class "Default")
      (node (ref "D2") (pin "4") (pinfunction "I/O_4") (pintype "passive+no_connect"))
    )
    (net (code "49") (name "unconnected-(D2-I{slash}O-Pad5)") (class "Default")
      (node (ref "D2") (pin "5") (pinfunction "I/O_5") (pintype "passive+no_connect"))
    )
    (net (code "50") (name "unconnected-(D2-NC-Pad6)") (class "Default")
      (node (ref "D2") (pin "6") (pinfunction "NC_6") (pintype "passive+no_connect"))
    )
    (net (code "51") (name "unconnected-(D2-NC-Pad7)") (class "Default")
      (node (ref "D2") (pin "7") (pinfunction "NC_7") (pintype "passive+no_connect"))
    )
    (net (code "52") (name "unconnected-(J2-SBU1-PadA8)") (class "Default")
      (node (ref "J2") (pin "A8") (pinfunction "SBU1_A8") (pintype "power_in+no_connect"))
    )
    (net (code "53") (name "unconnected-(J2-SBU2-PadB8)") (class "Default")
      (node (ref "J2") (pin "B8") (pinfunction "SBU2_B8") (pintype "power_in+no_connect"))
    )
    (net (code "54") (name "unconnected-(U1A-PME_MODE{slash}GPIO7-Pad43)") (class "Default")
      (node (ref "U1") (pin "43") (pinfunction "PME_MODE/GPIO7_43") (pintype "bidirectional+no_connect"))
    )
    (net (code "55") (name "unconnected-(U2-NC-Pad7)") (class "Default")
      (node (ref "U2") (pin "7") (pinfunction "NC_7") (pintype "passive+no_connect"))
    )
  )
)
